# ModbusSwitch_v1_0.net
KiCad netlist of a schematic drawn in EAGLE
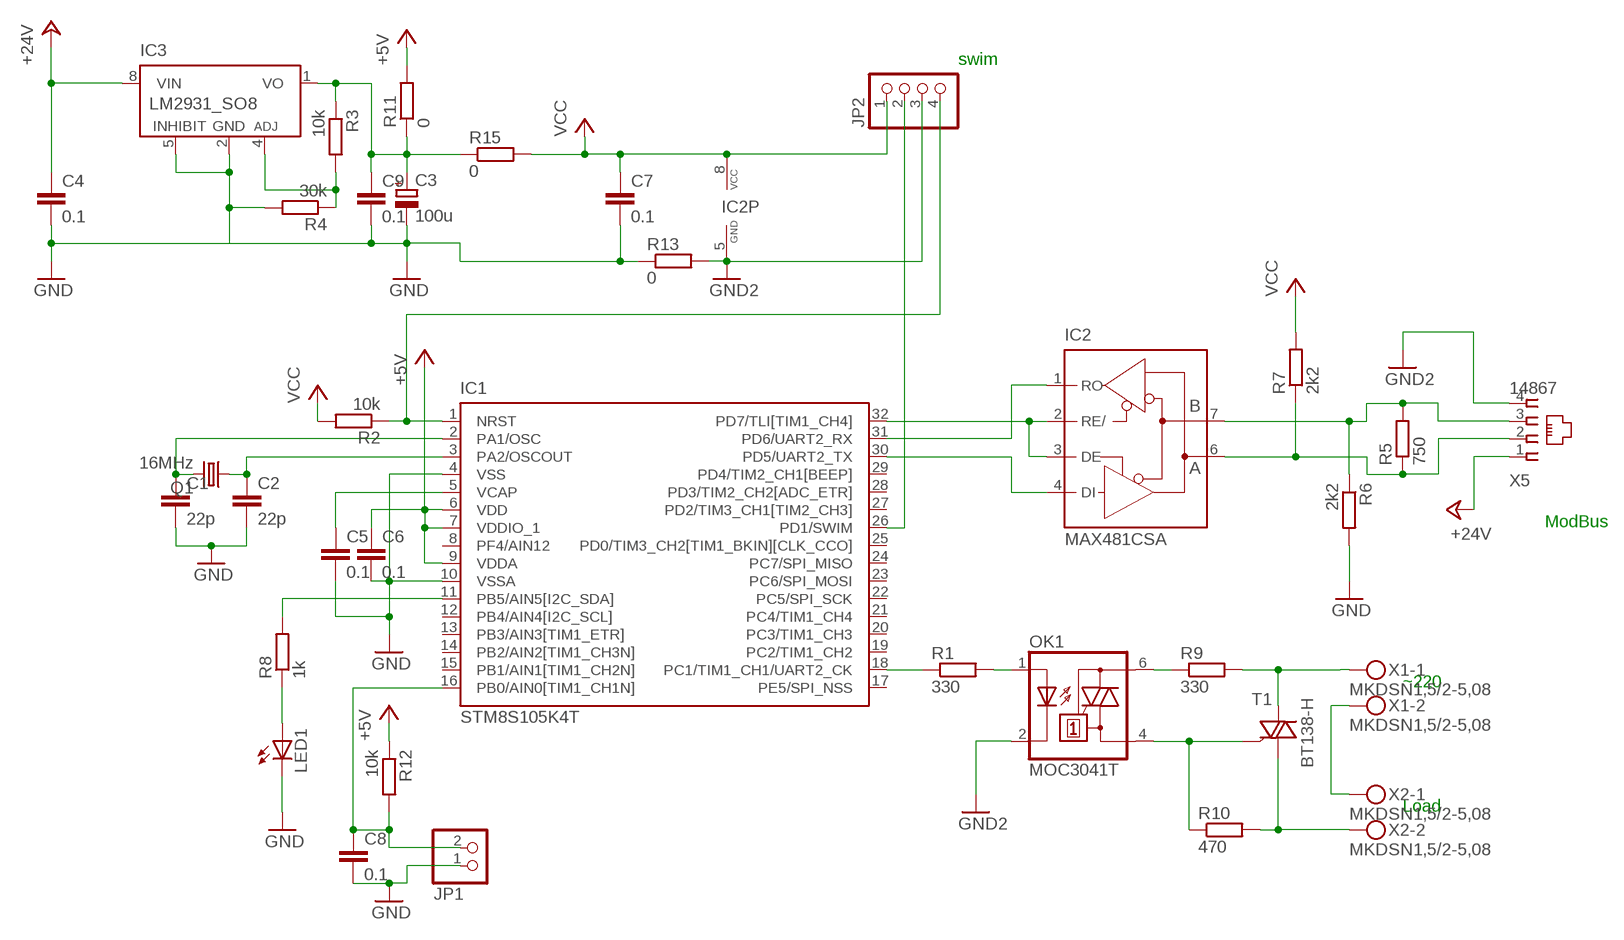
[diagram p0: schematic, sheet 1]

(export (version "E")
  (design (tool "Eeschema 10.0.6"))
  (components
    (comp (ref "C1")
      (value "22p")
      (footprint "eagle-import:C0603")
      (libsource (lib "eagle-import") (part "C-EUC0603"))
    )
    (comp (ref "C2")
      (value "22p")
      (footprint "eagle-import:C0603")
      (libsource (lib "eagle-import") (part "C-EUC0603"))
    )
    (comp (ref "C3")
      (value "100u")
      (footprint "eagle-import:E2,5-6")
      (libsource (lib "eagle-import") (part "CPOL-EUE2.5-6"))
    )
    (comp (ref "C4")
      (value "0.1")
      (footprint "eagle-import:C1206")
      (libsource (lib "eagle-import") (part "C-EUC1206"))
    )
    (comp (ref "C5")
      (value "0.1")
      (footprint "eagle-import:C0603")
      (libsource (lib "eagle-import") (part "C-EUC0603"))
    )
    (comp (ref "C6")
      (value "0.1")
      (footprint "eagle-import:C0603")
      (libsource (lib "eagle-import") (part "C-EUC0603"))
    )
    (comp (ref "C7")
      (value "0.1")
      (footprint "eagle-import:C0603")
      (libsource (lib "eagle-import") (part "C-EUC0603"))
    )
    (comp (ref "C8")
      (value "0.1")
      (footprint "eagle-import:C0603")
      (libsource (lib "eagle-import") (part "C-EUC0603"))
    )
    (comp (ref "C9")
      (value "0.1")
      (footprint "eagle-import:C0603")
      (libsource (lib "eagle-import") (part "C-EUC0603"))
    )
    (comp (ref "IC1")
      (value "STM8S105K4T")
      (footprint "eagle-import:LQFP32-7X7")
      (fields (field (name "MPN") "STM8S105K4T6C"))
      (libsource (lib "eagle-import") (part "STM8S105KT4"))
    )
    (comp (ref "IC2")
      (value "MAX481CSA")
      (footprint "eagle-import:SO08")
      (libsource (lib "eagle-import") (part "MAX481CSA"))
    )
    (comp (ref "IC3")
      (value "LM2931_SO8")
      (footprint "eagle-import:SO-08")
      (libsource (lib "eagle-import") (part "LM2931_SO8"))
    )
    (comp (ref "JP1")
      (value "PINHD-1X2/90")
      (footprint "eagle-import:1X02_90")
      (libsource (lib "eagle-import") (part "PINHD-1X2/90"))
    )
    (comp (ref "JP2")
      (value "PINHD-1X4")
      (footprint "eagle-import:1X04")
      (libsource (lib "eagle-import") (part "PINHD-1X4"))
    )
    (comp (ref "LED1")
      (value "LED3MM")
      (footprint "eagle-import:LED3MM")
      (libsource (lib "eagle-import") (part "LED3MM"))
    )
    (comp (ref "OK1")
      (value "MOC3041T")
      (footprint "eagle-import:DIL06B")
      (libsource (lib "eagle-import") (part "MOC30T41"))
    )
    (comp (ref "Q1")
      (value "16MHz")
      (footprint "eagle-import:HC49_S")
      (libsource (lib "eagle-import") (part "CRYSTALHC49S"))
    )
    (comp (ref "R1")
      (value "330")
      (footprint "eagle-import:R0805")
      (libsource (lib "eagle-import") (part "resistor_R-EU_R0805"))
    )
    (comp (ref "R2")
      (value "10k")
      (footprint "eagle-import:R0603")
      (libsource (lib "eagle-import") (part "resistor_R-EU_R0603"))
    )
    (comp (ref "R3")
      (value "10k")
      (footprint "eagle-import:R0603")
      (libsource (lib "eagle-import") (part "resistor_R-EU_R0603"))
    )
    (comp (ref "R4")
      (value "30k")
      (footprint "eagle-import:R0603")
      (libsource (lib "eagle-import") (part "resistor_R-EU_R0603"))
    )
    (comp (ref "R5")
      (value "750")
      (footprint "eagle-import:R0603")
      (libsource (lib "eagle-import") (part "resistor_R-EU_R0603"))
    )
    (comp (ref "R6")
      (value "2k2")
      (footprint "eagle-import:R0603")
      (libsource (lib "eagle-import") (part "resistor_R-EU_R0603"))
    )
    (comp (ref "R7")
      (value "2k2")
      (footprint "eagle-import:R0603")
      (libsource (lib "eagle-import") (part "resistor_R-EU_R0603"))
    )
    (comp (ref "R8")
      (value "1k")
      (footprint "eagle-import:R0603")
      (libsource (lib "eagle-import") (part "resistor_R-EU_R0603"))
    )
    (comp (ref "R9")
      (value "330")
      (footprint "eagle-import:R1206")
      (libsource (lib "eagle-import") (part "resistor_R-EU_R1206"))
    )
    (comp (ref "R10")
      (value "470")
      (footprint "eagle-import:R1206")
      (libsource (lib "eagle-import") (part "resistor_R-EU_R1206"))
    )
    (comp (ref "R11")
      (value "0")
      (footprint "eagle-import:R1206")
      (libsource (lib "eagle-import") (part "R-EU_R1206"))
    )
    (comp (ref "R12")
      (value "10k")
      (footprint "eagle-import:R0603")
      (libsource (lib "eagle-import") (part "resistor_R-EU_R0603"))
    )
    (comp (ref "R13")
      (value "0")
      (footprint "eagle-import:R1206")
      (libsource (lib "eagle-import") (part "R-EU_R1206"))
    )
    (comp (ref "R15")
      (value "0")
      (footprint "eagle-import:R1206")
      (libsource (lib "eagle-import") (part "R-EU_R1206"))
    )
    (comp (ref "T1")
      (value "BT138-H")
      (footprint "eagle-import:TO220BH")
      (libsource (lib "eagle-import") (part "BT138-H"))
    )
    (comp (ref "X1")
      (value "MKDSN1,5/2-5,08")
      (footprint "eagle-import:MKDSN1,5_2-5,08")
      (fields (field (name "MPN") "MKDSN 1,5/2-5.08"))
      (libsource (lib "eagle-import") (part "MKDSN1,5/2-5,08"))
    )
    (comp (ref "X2")
      (value "MKDSN1,5/2-5,08")
      (footprint "eagle-import:MKDSN1,5_2-5,08")
      (fields (field (name "MPN") "MKDSN 1,5/2-5.08"))
      (libsource (lib "eagle-import") (part "MKDSN1,5/2-5,08"))
    )
    (comp (ref "X5")
      (value "14867")
      (footprint "eagle-import:14867")
      (libsource (lib "eagle-import") (part "14867"))
    )
  )
  (nets
    (net (code "1") (name "+5V") (class "Default")
      (node (ref "C6") (pin "1") (pinfunction "1_1") (pintype "passive"))
      (node (ref "IC1") (pin "6") (pinfunction "VDD_6") (pintype "power_in"))
      (node (ref "IC1") (pin "7") (pinfunction "VDDIO_1_7") (pintype "power_in"))
      (node (ref "IC1") (pin "9") (pinfunction "VDDA_9") (pintype "power_in"))
      (node (ref "R11") (pin "2") (pinfunction "2_2") (pintype "passive"))
      (node (ref "R12") (pin "1") (pinfunction "1_1") (pintype "passive"))
    )
    (net (code "2") (name "+24V") (class "Default")
      (node (ref "C4") (pin "1") (pinfunction "1_1") (pintype "passive"))
      (node (ref "IC3") (pin "8") (pinfunction "VIN_8") (pintype "input"))
      (node (ref "X5") (pin "1") (pinfunction "1_1") (pintype "passive"))
    )
    (net (code "3") (name "GND") (class "Default")
      (node (ref "C1") (pin "2") (pinfunction "2_2") (pintype "passive"))
      (node (ref "C2") (pin "2") (pinfunction "2_2") (pintype "passive"))
      (node (ref "C3") (pin "-") (pinfunction "-_-") (pintype "passive"))
      (node (ref "C4") (pin "2") (pinfunction "2_2") (pintype "passive"))
      (node (ref "C5") (pin "2") (pinfunction "2_2") (pintype "passive"))
      (node (ref "C6") (pin "2") (pinfunction "2_2") (pintype "passive"))
      (node (ref "C7") (pin "2") (pinfunction "2_2") (pintype "passive"))
      (node (ref "C8") (pin "2") (pinfunction "2_2") (pintype "passive"))
      (node (ref "C9") (pin "2") (pinfunction "2_2") (pintype "passive"))
      (node (ref "IC1") (pin "10") (pinfunction "VSSA_10") (pintype "power_in"))
      (node (ref "IC1") (pin "4") (pinfunction "VSS_4") (pintype "power_in"))
      (node (ref "IC3") (pin "2") (pinfunction "GND_2") (pintype "power_in"))
      (node (ref "IC3") (pin "5") (pinfunction "INHIBIT_5") (pintype "bidirectional"))
      (node (ref "JP1") (pin "1") (pinfunction "1_1") (pintype "passive"))
      (node (ref "LED1") (pin "K") (pinfunction "C_K") (pintype "passive"))
      (node (ref "R13") (pin "1") (pinfunction "1_1") (pintype "passive"))
      (node (ref "R4") (pin "2") (pinfunction "2_2") (pintype "passive"))
      (node (ref "R6") (pin "2") (pinfunction "2_2") (pintype "passive"))
    )
    (net (code "4") (name "GND2") (class "Default")
      (node (ref "IC2") (pin "5") (pinfunction "GND_5") (pintype "power_in"))
      (node (ref "JP2") (pin "3") (pinfunction "3_3") (pintype "passive"))
      (node (ref "OK1") (pin "2") (pinfunction "C_2") (pintype "passive"))
      (node (ref "R13") (pin "2") (pinfunction "2_2") (pintype "passive"))
      (node (ref "X5") (pin "4") (pinfunction "4_4") (pintype "passive"))
    )
    (net (code "5") (name "Net-(IC1-NRST)") (class "Default")
      (node (ref "IC1") (pin "1") (pinfunction "NRST_1") (pintype "bidirectional"))
      (node (ref "JP2") (pin "4") (pinfunction "4_4") (pintype "passive"))
      (node (ref "R2") (pin "1") (pinfunction "1_1") (pintype "passive"))
    )
    (net (code "6") (name "Net-(IC1-PA1{slash}OSC)") (class "Default")
      (node (ref "C1") (pin "1") (pinfunction "1_1") (pintype "passive"))
      (node (ref "IC1") (pin "2") (pinfunction "PA1/OSC_2") (pintype "bidirectional"))
      (node (ref "Q1") (pin "2") (pinfunction "2_2") (pintype "passive"))
    )
    (net (code "7") (name "Net-(IC1-PA2{slash}OSCOUT)") (class "Default")
      (node (ref "C2") (pin "1") (pinfunction "1_1") (pintype "passive"))
      (node (ref "IC1") (pin "3") (pinfunction "PA2/OSCOUT_3") (pintype "bidirectional"))
      (node (ref "Q1") (pin "1") (pinfunction "1_1") (pintype "passive"))
    )
    (net (code "8") (name "Net-(IC1-PB0{slash}AIN0[TIM1_CH1N])") (class "Default")
      (node (ref "C8") (pin "1") (pinfunction "1_1") (pintype "passive"))
      (node (ref "IC1") (pin "16") (pinfunction "PB0/AIN0[TIM1_CH1N]_16") (pintype "bidirectional"))
      (node (ref "JP1") (pin "2") (pinfunction "2_2") (pintype "passive"))
      (node (ref "R12") (pin "2") (pinfunction "2_2") (pintype "passive"))
    )
    (net (code "9") (name "Net-(IC1-PB5{slash}AIN5[I2C_SDA])") (class "Default")
      (node (ref "IC1") (pin "11") (pinfunction "PB5/AIN5[I2C_SDA]_11") (pintype "bidirectional"))
      (node (ref "R8") (pin "2") (pinfunction "2_2") (pintype "passive"))
    )
    (net (code "10") (name "Net-(IC1-PC1{slash}TIM1_CH1{slash}UART2_CK)") (class "Default")
      (node (ref "IC1") (pin "18") (pinfunction "PC1/TIM1_CH1/UART2_CK_18") (pintype "bidirectional"))
      (node (ref "R1") (pin "1") (pinfunction "1_1") (pintype "passive"))
    )
    (net (code "11") (name "Net-(IC1-PD1{slash}SWIM)") (class "Default")
      (node (ref "IC1") (pin "26") (pinfunction "PD1/SWIM_26") (pintype "bidirectional"))
      (node (ref "JP2") (pin "2") (pinfunction "2_2") (pintype "passive"))
    )
    (net (code "12") (name "Net-(IC1-PD5{slash}UART2_TX)") (class "Default")
      (node (ref "IC1") (pin "30") (pinfunction "PD5/UART2_TX_30") (pintype "bidirectional"))
      (node (ref "IC2") (pin "4") (pinfunction "DI_4") (pintype "input"))
    )
    (net (code "13") (name "Net-(IC1-PD6{slash}UART2_RX)") (class "Default")
      (node (ref "IC1") (pin "31") (pinfunction "PD6/UART2_RX_31") (pintype "bidirectional"))
      (node (ref "IC2") (pin "1") (pinfunction "RO_1") (pintype "output"))
    )
    (net (code "14") (name "Net-(IC1-PD7{slash}TLI[TIM1_CH4])") (class "Default")
      (node (ref "IC1") (pin "32") (pinfunction "PD7/TLI[TIM1_CH4]_32") (pintype "bidirectional"))
      (node (ref "IC2") (pin "2") (pinfunction "RE/_2") (pintype "input"))
      (node (ref "IC2") (pin "3") (pinfunction "DE_3") (pintype "input"))
    )
    (net (code "15") (name "Net-(IC1-VCAP)") (class "Default")
      (node (ref "C5") (pin "1") (pinfunction "1_1") (pintype "passive"))
      (node (ref "IC1") (pin "5") (pinfunction "VCAP_5") (pintype "power_in"))
    )
    (net (code "16") (name "Net-(IC2A-A)") (class "Default")
      (node (ref "IC2") (pin "6") (pinfunction "A_6") (pintype "passive"))
      (node (ref "R5") (pin "1") (pinfunction "1_1") (pintype "passive"))
      (node (ref "R7") (pin "1") (pinfunction "1_1") (pintype "passive"))
      (node (ref "X5") (pin "2") (pinfunction "2_2") (pintype "passive"))
    )
    (net (code "17") (name "Net-(IC2A-B)") (class "Default")
      (node (ref "IC2") (pin "7") (pinfunction "B_7") (pintype "passive"))
      (node (ref "R5") (pin "2") (pinfunction "2_2") (pintype "passive"))
      (node (ref "R6") (pin "1") (pinfunction "1_1") (pintype "passive"))
      (node (ref "X5") (pin "3") (pinfunction "3_3") (pintype "passive"))
    )
    (net (code "18") (name "Net-(IC3A-ADJ)") (class "Default")
      (node (ref "IC3") (pin "4") (pinfunction "ADJ_4") (pintype "bidirectional"))
      (node (ref "R3") (pin "2") (pinfunction "2_2") (pintype "passive"))
      (node (ref "R4") (pin "1") (pinfunction "1_1") (pintype "passive"))
    )
    (net (code "19") (name "Net-(IC3A-VO)") (class "Default")
      (node (ref "C3") (pin "+") (pinfunction "+_+") (pintype "passive"))
      (node (ref "C9") (pin "1") (pinfunction "1_1") (pintype "passive"))
      (node (ref "IC3") (pin "1") (pinfunction "VO_1") (pintype "output"))
      (node (ref "R11") (pin "1") (pinfunction "1_1") (pintype "passive"))
      (node (ref "R15") (pin "1") (pinfunction "1_1") (pintype "passive"))
      (node (ref "R3") (pin "1") (pinfunction "1_1") (pintype "passive"))
    )
    (net (code "20") (name "Net-(LED1-PadA)") (class "Default")
      (node (ref "LED1") (pin "A") (pinfunction "A_A") (pintype "passive"))
      (node (ref "R8") (pin "1") (pinfunction "1_1") (pintype "passive"))
    )
    (net (code "21") (name "Net-(OK1-A)") (class "Default")
      (node (ref "OK1") (pin "1") (pinfunction "A_1") (pintype "passive"))
      (node (ref "R1") (pin "2") (pinfunction "2_2") (pintype "passive"))
    )
    (net (code "22") (name "Net-(OK1-A1)") (class "Default")
      (node (ref "OK1") (pin "4") (pinfunction "A1_4") (pintype "passive"))
      (node (ref "R10") (pin "1") (pinfunction "1_1") (pintype "passive"))
      (node (ref "T1") (pin "G") (pinfunction "G_G") (pintype "passive"))
    )
    (net (code "23") (name "Net-(OK1-A2)") (class "Default")
      (node (ref "OK1") (pin "6") (pinfunction "A2_6") (pintype "passive"))
      (node (ref "R9") (pin "1") (pinfunction "1_1") (pintype "passive"))
    )
    (net (code "24") (name "Net-(T1-A1)") (class "Default")
      (node (ref "R10") (pin "2") (pinfunction "2_2") (pintype "passive"))
      (node (ref "T1") (pin "T1") (pinfunction "A1_T1") (pintype "passive"))
      (node (ref "X2") (pin "2") (pinfunction "KL_2") (pintype "passive"))
    )
    (net (code "25") (name "Net-(T1-A2)") (class "Default")
      (node (ref "R9") (pin "2") (pinfunction "2_2") (pintype "passive"))
      (node (ref "T1") (pin "T2") (pinfunction "A2_T2") (pintype "passive"))
      (node (ref "X1") (pin "1") (pinfunction "KL_1") (pintype "passive"))
    )
    (net (code "26") (name "Net-(X1B-KL)") (class "Default")
      (node (ref "X1") (pin "2") (pinfunction "KL_2") (pintype "passive"))
      (node (ref "X2") (pin "1") (pinfunction "KL_1") (pintype "passive"))
    )
    (net (code "27") (name "VCC") (class "Default")
      (node (ref "C7") (pin "1") (pinfunction "1_1") (pintype "passive"))
      (node (ref "IC2") (pin "8") (pinfunction "VCC_8") (pintype "power_in"))
      (node (ref "JP2") (pin "1") (pinfunction "1_1") (pintype "passive"))
      (node (ref "R15") (pin "2") (pinfunction "2_2") (pintype "passive"))
      (node (ref "R2") (pin "2") (pinfunction "2_2") (pintype "passive"))
      (node (ref "R7") (pin "2") (pinfunction "2_2") (pintype "passive"))
    )
    (net (code "28") (name "unconnected-(IC1-PB1{slash}AIN1[TIM1_CH2N]-Pad15)") (class "Default")
      (node (ref "IC1") (pin "15") (pinfunction "PB1/AIN1[TIM1_CH2N]_15") (pintype "bidirectional"))
    )
    (net (code "29") (name "unconnected-(IC1-PB2{slash}AIN2[TIM1_CH3N]-Pad14)") (class "Default")
      (node (ref "IC1") (pin "14") (pinfunction "PB2/AIN2[TIM1_CH3N]_14") (pintype "bidirectional"))
    )
    (net (code "30") (name "unconnected-(IC1-PB3{slash}AIN3[TIM1_ETR]-Pad13)") (class "Default")
      (node (ref "IC1") (pin "13") (pinfunction "PB3/AIN3[TIM1_ETR]_13") (pintype "bidirectional"))
    )
    (net (code "31") (name "unconnected-(IC1-PB4{slash}AIN4[I2C_SCL]-Pad12)") (class "Default")
      (node (ref "IC1") (pin "12") (pinfunction "PB4/AIN4[I2C_SCL]_12") (pintype "bidirectional"))
    )
    (net (code "32") (name "unconnected-(IC1-PC2{slash}TIM1_CH2-Pad19)") (class "Default")
      (node (ref "IC1") (pin "19") (pinfunction "PC2/TIM1_CH2_19") (pintype "bidirectional"))
    )
    (net (code "33") (name "unconnected-(IC1-PC3{slash}TIM1_CH3-Pad20)") (class "Default")
      (node (ref "IC1") (pin "20") (pinfunction "PC3/TIM1_CH3_20") (pintype "bidirectional"))
    )
    (net (code "34") (name "unconnected-(IC1-PC4{slash}TIM1_CH4-Pad21)") (class "Default")
      (node (ref "IC1") (pin "21") (pinfunction "PC4/TIM1_CH4_21") (pintype "bidirectional"))
    )
    (net (code "35") (name "unconnected-(IC1-PC5{slash}SPI_SCK-Pad22)") (class "Default")
      (node (ref "IC1") (pin "22") (pinfunction "PC5/SPI_SCK_22") (pintype "bidirectional"))
    )
    (net (code "36") (name "unconnected-(IC1-PC6{slash}SPI_MOSI-Pad23)") (class "Default")
      (node (ref "IC1") (pin "23") (pinfunction "PC6/SPI_MOSI_23") (pintype "bidirectional"))
    )
    (net (code "37") (name "unconnected-(IC1-PC7{slash}SPI_MISO-Pad24)") (class "Default")
      (node (ref "IC1") (pin "24") (pinfunction "PC7/SPI_MISO_24") (pintype "bidirectional"))
    )
    (net (code "38") (name "unconnected-(IC1-PD0{slash}TIM3_CH2[TIM1_BKIN][CLK_CCO]-Pad25)") (class "Default")
      (node (ref "IC1") (pin "25") (pinfunction "PD0/TIM3_CH2[TIM1_BKIN][CLK_CCO]_25") (pintype "bidirectional"))
    )
    (net (code "39") (name "unconnected-(IC1-PD2{slash}TIM3_CH1[TIM2_CH3]-Pad27)") (class "Default")
      (node (ref "IC1") (pin "27") (pinfunction "PD2/TIM3_CH1[TIM2_CH3]_27") (pintype "bidirectional"))
    )
    (net (code "40") (name "unconnected-(IC1-PD3{slash}TIM2_CH2[ADC_ETR]-Pad28)") (class "Default")
      (node (ref "IC1") (pin "28") (pinfunction "PD3/TIM2_CH2[ADC_ETR]_28") (pintype "bidirectional"))
    )
    (net (code "41") (name "unconnected-(IC1-PD4{slash}TIM2_CH1[BEEP]-Pad29)") (class "Default")
      (node (ref "IC1") (pin "29") (pinfunction "PD4/TIM2_CH1[BEEP]_29") (pintype "bidirectional"))
    )
    (net (code "42") (name "unconnected-(IC1-PE5{slash}SPI_NSS-Pad17)") (class "Default")
      (node (ref "IC1") (pin "17") (pinfunction "PE5/SPI_NSS_17") (pintype "bidirectional"))
    )
    (net (code "43") (name "unconnected-(IC1-PF4{slash}AIN12-Pad8)") (class "Default")
      (node (ref "IC1") (pin "8") (pinfunction "PF4/AIN12_8") (pintype "bidirectional"))
    )
  )
)
